# SMPS_1000mA_-_LM22672.net
KiCad netlist of a schematic drawn in Altium Designer
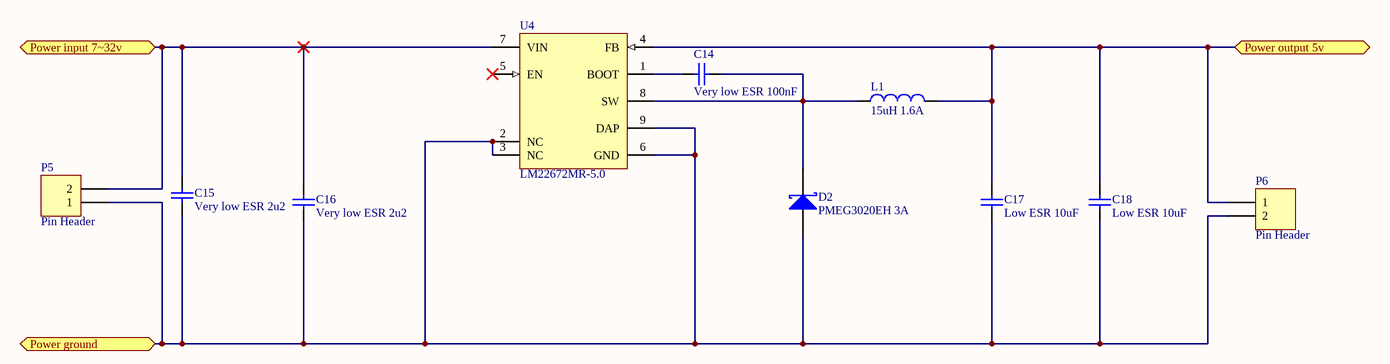
[diagram p0: SMPS 1000mA - LM22672.SchDoc]

(export (version "E")
  (design (tool "Eeschema 10.0.6"))
  (components
    (comp (ref "C14")
      (value "Very low ESR 100nF")
      (footprint "C0805")
      (fields
        (field (name "PART NUMBER") "0.01uF-0805-X7R")
        (field (name "VOLTAGE") "50V")
        (field (name "TOLERANCE") "0.1")
        (field (name "AUTHOR") "Willem Pietersz")
      )
      (libsource (lib "OurDb") (part "cap_NonPolar"))
    )
    (comp (ref "C15")
      (value "Very low ESR 2u2")
      (footprint "C1210")
      (fields
        (field (name "PART NUMBER") "2.2uF-1210-X7R")
        (field (name "VOLTAGE") "50V")
        (field (name "TOLERANCE") "0.1")
        (field (name "AUTHOR") "Willem Pietersz")
      )
      (libsource (lib "OurDb") (part "cap_NonPolar"))
    )
    (comp (ref "C16")
      (value "Very low ESR 2u2")
      (footprint "C1210")
      (fields
        (field (name "PART NUMBER") "2.2uF-1210-X7R")
        (field (name "VOLTAGE") "50V")
        (field (name "TOLERANCE") "0.1")
        (field (name "AUTHOR") "Willem Pietersz")
      )
      (libsource (lib "OurDb") (part "cap_NonPolar"))
    )
    (comp (ref "C17")
      (value "Low ESR 10uF")
      (footprint "C1210")
      (fields
        (field (name "PART NUMBER") "10uF-1210-X5R")
        (field (name "VOLTAGE") "10V")
        (field (name "TOLERANCE") "0.1")
        (field (name "AUTHOR") "Willem Pietersz")
      )
      (libsource (lib "OurDb") (part "cap_NonPolar"))
    )
    (comp (ref "C18")
      (value "Low ESR 10uF")
      (footprint "C1210")
      (fields
        (field (name "PART NUMBER") "10uF-1210-X5R")
        (field (name "VOLTAGE") "10V")
        (field (name "TOLERANCE") "0.1")
        (field (name "AUTHOR") "Willem Pietersz")
      )
      (libsource (lib "OurDb") (part "cap_NonPolar"))
    )
    (comp (ref "D2")
      (value "PMEG3020EH 3A")
      (footprint "SOD123F")
      (fields (field (name "PART NUMBER") "PMEG3020EH") (field (name "VOLTAGE") "30V"))
      (libsource (lib "OurDb") (part "SCHOTTKY"))
    )
    (comp (ref "L1")
      (value "15uH 1.6A")
      (footprint "Square_7.3x7.3x4.5")
      (description "Inductor")
      (fields (field (name "PART NUMBER") "15uH-Shield-1.6A-Wurth") (field (name "Comment") "inductor"))
      (libsource (lib "OurDb") (part "inductor"))
    )
    (comp (ref "P5")
      (value "Pin Header")
      (footprint "PH1x2_2.54")
      (description "Con1x2")
      (fields (field (name "PART NUMBER") "PH1x2") (field (name "AUTHOR") "Willy Pietersz"))
      (libsource (lib "OurDb") (part "Con1x2"))
    )
    (comp (ref "P6")
      (value "Pin Header")
      (footprint "PH1x2_2.54")
      (description "Con1x2")
      (fields (field (name "PART NUMBER") "PH1x2") (field (name "AUTHOR") "Willy Pietersz"))
      (libsource (lib "") (part "Con1x2_1"))
    )
    (comp (ref "U4")
      (value "LM22672MR-5.0")
      (footprint "MRA08B_N")
      (description "Power, 500mA SIMPLE SWITCHER, Step-Down Voltage Regulator with Precision Enable")
      (fields
        (field (name "PARTNUMBER") "LM22674MR-5.0")
        (field (name "MANUFACTURER") "National Semiconductor")
        (field (name "PUBLISHER") "Altium Limited")
      )
      (libsource (lib "AltiumDatabaseSelection") (part "LM22674MR-5.0"))
    )
  )
  (nets
    (net (code "1") (name "/Power ground") (class "Default")
      (node (ref "C15") (pin "1") (pinfunction "1_1") (pintype "passive"))
      (node (ref "C16") (pin "1") (pinfunction "1_1") (pintype "passive"))
      (node (ref "C17") (pin "1") (pinfunction "1_1") (pintype "passive"))
      (node (ref "C18") (pin "1") (pinfunction "1_1") (pintype "passive"))
      (node (ref "D2") (pin "1") (pinfunction "1_1") (pintype "passive"))
      (node (ref "P5") (pin "1") (pinfunction "1_1") (pintype "passive"))
      (node (ref "P6") (pin "2") (pinfunction "2_2") (pintype "passive"))
      (node (ref "U4") (pin "2") (pinfunction "NC_2") (pintype "passive"))
      (node (ref "U4") (pin "3") (pinfunction "NC_3") (pintype "passive"))
      (node (ref "U4") (pin "6") (pinfunction "GND_6") (pintype "power_in"))
      (node (ref "U4") (pin "9") (pinfunction "DAP_9") (pintype "power_in"))
    )
    (net (code "2") (name "/Power input 7~32v") (class "Default")
      (node (ref "C15") (pin "2") (pinfunction "2_2") (pintype "passive"))
      (node (ref "C16") (pin "2") (pinfunction "2_2") (pintype "passive"))
      (node (ref "P5") (pin "2") (pinfunction "2_2") (pintype "passive"))
      (node (ref "U4") (pin "7") (pinfunction "VIN_7") (pintype "power_in"))
    )
    (net (code "3") (name "/Power output 5v") (class "Default")
      (node (ref "C17") (pin "2") (pinfunction "2_2") (pintype "passive"))
      (node (ref "C18") (pin "2") (pinfunction "2_2") (pintype "passive"))
      (node (ref "L1") (pin "2") (pinfunction "2_2") (pintype "passive"))
      (node (ref "P6") (pin "1") (pinfunction "1_1") (pintype "passive"))
      (node (ref "U4") (pin "4") (pinfunction "FB_4") (pintype "input"))
    )
    (net (code "4") (name "Net-(U4-BOOT)") (class "Default")
      (node (ref "C14") (pin "1") (pinfunction "1_1") (pintype "passive"))
      (node (ref "U4") (pin "1") (pinfunction "BOOT_1") (pintype "passive"))
    )
    (net (code "5") (name "Net-(U4-SW)") (class "Default")
      (node (ref "C14") (pin "2") (pinfunction "2_2") (pintype "passive"))
      (node (ref "D2") (pin "2") (pinfunction "2_2") (pintype "passive"))
      (node (ref "L1") (pin "1") (pinfunction "1_1") (pintype "passive"))
      (node (ref "U4") (pin "8") (pinfunction "SW_8") (pintype "power_in"))
    )
    (net (code "6") (name "unconnected-(U4-EN-Pad5)") (class "Default")
      (node (ref "U4") (pin "5") (pinfunction "EN_5") (pintype "input+no_connect"))
    )
  )
)
